# Adjustable_Positive_SupplyV3Switch.net
KiCad netlist of a schematic drawn in EAGLE
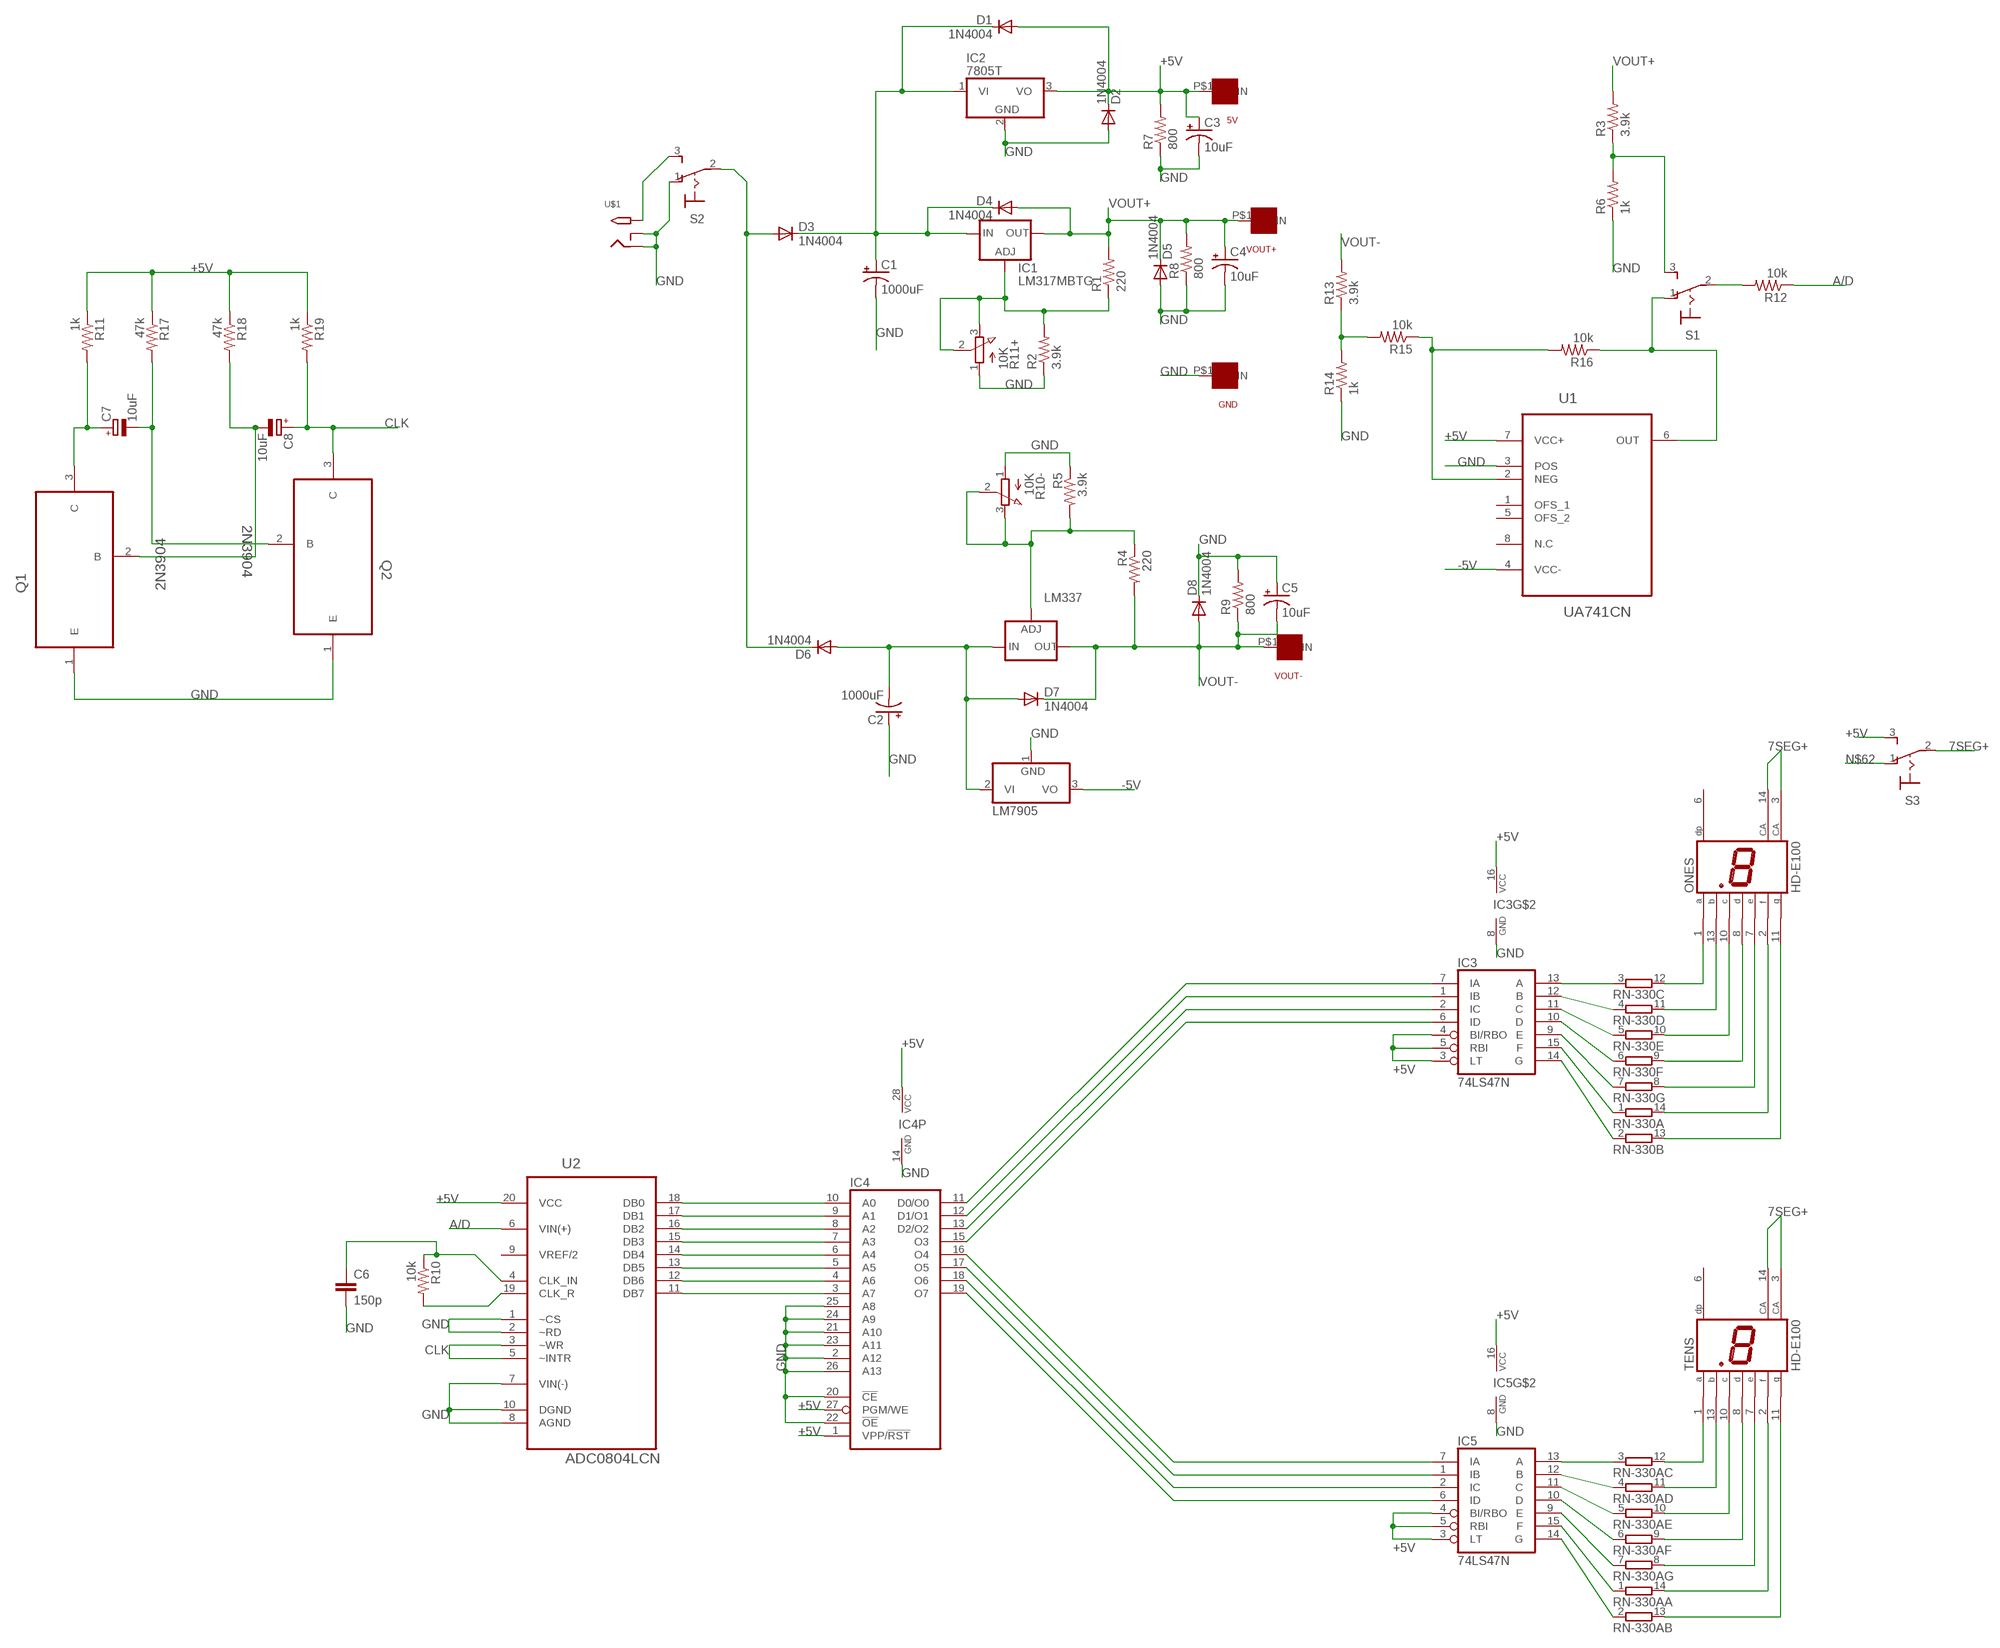
[diagram p0: schematic, sheet 1]

(export (version "E")
  (design (tool "Eeschema 10.0.6"))
  (components
    (comp (ref "5V")
      (value "TURRENT_TERMINAL")
      (footprint "eagle-import:TURRET_CONNECTOR")
      (libsource (lib "eagle-import") (part "TURRENT_TERMINAL"))
    )
    (comp (ref "C1")
      (value "1000uF")
      (footprint "eagle-import:E7,5-16")
      (libsource (lib "eagle-import") (part "CPOL-USE7.5-16"))
    )
    (comp (ref "C2")
      (value "1000uF")
      (footprint "eagle-import:E7,5-16")
      (libsource (lib "eagle-import") (part "CPOL-USE7.5-16"))
    )
    (comp (ref "C3")
      (value "10uF")
      (footprint "eagle-import:E2,5-5")
      (libsource (lib "eagle-import") (part "rcl_CPOL-USE2.5-5"))
    )
    (comp (ref "C4")
      (value "10uF")
      (footprint "eagle-import:E2,5-5")
      (libsource (lib "eagle-import") (part "rcl_CPOL-USE2.5-5"))
    )
    (comp (ref "C5")
      (value "10uF")
      (footprint "eagle-import:E2,5-5")
      (libsource (lib "eagle-import") (part "rcl_CPOL-USE2.5-5"))
    )
    (comp (ref "C6")
      (value "150p")
      (footprint "eagle-import:C025-025X050")
      (libsource (lib "eagle-import") (part "C-EU025-025X050"))
    )
    (comp (ref "C7")
      (value "10uF")
      (footprint "eagle-import:B45181B")
      (libsource (lib "eagle-import") (part "CPOL-EUB45181B"))
    )
    (comp (ref "C8")
      (value "10uF")
      (footprint "eagle-import:B45181B")
      (libsource (lib "eagle-import") (part "CPOL-EUB45181B"))
    )
    (comp (ref "D1")
      (value "1N4004")
      (footprint "eagle-import:DO41-10")
      (libsource (lib "eagle-import") (part "1N4004"))
    )
    (comp (ref "D2")
      (value "1N4004")
      (footprint "eagle-import:DO41-10")
      (libsource (lib "eagle-import") (part "1N4004"))
    )
    (comp (ref "D3")
      (value "1N4004")
      (footprint "eagle-import:DO41-10")
      (libsource (lib "eagle-import") (part "1N4004"))
    )
    (comp (ref "D4")
      (value "1N4004")
      (footprint "eagle-import:DO41-10")
      (libsource (lib "eagle-import") (part "1N4004"))
    )
    (comp (ref "D5")
      (value "1N4004")
      (footprint "eagle-import:DO41-10")
      (libsource (lib "eagle-import") (part "1N4004"))
    )
    (comp (ref "D6")
      (value "1N4004")
      (footprint "eagle-import:DO41-10")
      (libsource (lib "eagle-import") (part "1N4004"))
    )
    (comp (ref "D7")
      (value "1N4004")
      (footprint "eagle-import:DO41-10")
      (libsource (lib "eagle-import") (part "1N4004"))
    )
    (comp (ref "D8")
      (value "1N4004")
      (footprint "eagle-import:DO41-10")
      (libsource (lib "eagle-import") (part "1N4004"))
    )
    (comp (ref "GND")
      (value "TURRENT_TERMINAL")
      (footprint "eagle-import:TURRET_CONNECTOR")
      (libsource (lib "eagle-import") (part "TURRENT_TERMINAL"))
    )
    (comp (ref "IC1")
      (value "LM317MBTG")
      (footprint "eagle-import:TO220L1")
      (libsource (lib "eagle-import") (part "LM317?MBTG"))
    )
    (comp (ref "IC2")
      (value "7805T")
      (footprint "eagle-import:TO220H")
      (libsource (lib "eagle-import") (part "78T05"))
    )
    (comp (ref "IC3")
      (value "74LS47N")
      (footprint "eagle-import:DIL16")
      (libsource (lib "eagle-import") (part "7447NLS"))
    )
    (comp (ref "IC4")
      (value "27011")
      (footprint "eagle-import:DIL28")
      (libsource (lib "eagle-import") (part "27011"))
    )
    (comp (ref "IC5")
      (value "74LS47N")
      (footprint "eagle-import:DIL16")
      (libsource (lib "eagle-import") (part "7447NLS"))
    )
    (comp (ref "LM337")
      (value "LM337TL")
      (footprint "eagle-import:337TL")
      (libsource (lib "eagle-import") (part "LM337TL"))
    )
    (comp (ref "LM7905")
      (value "7905T")
      (footprint "eagle-import:TO220H")
      (libsource (lib "eagle-import") (part "79T05"))
    )
    (comp (ref "ONES")
      (value "HD-E100")
      (footprint "eagle-import:HDSP-I")
      (libsource (lib "eagle-import") (part "HD-E100"))
    )
    (comp (ref "Q1")
      (value "2N3904")
      (footprint "eagle-import:TO254P508X877-3")
      (libsource (lib "eagle-import") (part "2N3904"))
    )
    (comp (ref "Q2")
      (value "2N3904")
      (footprint "eagle-import:TO254P508X877-3")
      (libsource (lib "eagle-import") (part "2N3904"))
    )
    (comp (ref "R1")
      (value "220")
      (footprint "eagle-import:0411_15")
      (libsource (lib "eagle-import") (part "R-US_0411/15"))
    )
    (comp (ref "R2")
      (value "3.9k")
      (footprint "eagle-import:0411_15")
      (libsource (lib "eagle-import") (part "R-US_0411/15"))
    )
    (comp (ref "R3")
      (value "3.9k")
      (footprint "eagle-import:0411_15")
      (libsource (lib "eagle-import") (part "R-US_0411/15"))
    )
    (comp (ref "R4")
      (value "220")
      (footprint "eagle-import:0411_15")
      (libsource (lib "eagle-import") (part "R-US_0411/15"))
    )
    (comp (ref "R5")
      (value "3.9k")
      (footprint "eagle-import:0411_15")
      (libsource (lib "eagle-import") (part "R-US_0411/15"))
    )
    (comp (ref "R6")
      (value "1k")
      (footprint "eagle-import:0411_15")
      (libsource (lib "eagle-import") (part "R-US_0411/15"))
    )
    (comp (ref "R7")
      (value "800")
      (footprint "eagle-import:0411_15")
      (libsource (lib "eagle-import") (part "R-US_0411/15"))
    )
    (comp (ref "R8")
      (value "800")
      (footprint "eagle-import:0411_15")
      (libsource (lib "eagle-import") (part "R-US_0411/15"))
    )
    (comp (ref "R9")
      (value "800")
      (footprint "eagle-import:0411_15")
      (libsource (lib "eagle-import") (part "R-US_0411/15"))
    )
    (comp (ref "R10")
      (value "10k")
      (footprint "eagle-import:0411_15")
      (libsource (lib "eagle-import") (part "R-US_0411/15"))
    )
    (comp (ref "R10-")
      (value "10K")
      (footprint "eagle-import:EVUE")
      (libsource (lib "eagle-import") (part "EVUE2A"))
    )
    (comp (ref "R11")
      (value "1k")
      (footprint "eagle-import:0411_15")
      (libsource (lib "eagle-import") (part "R-US_0411/15"))
    )
    (comp (ref "R11+")
      (value "10K")
      (footprint "eagle-import:EVUE")
      (libsource (lib "eagle-import") (part "EVUE2A"))
    )
    (comp (ref "R12")
      (value "10k")
      (footprint "eagle-import:0411_15")
      (libsource (lib "eagle-import") (part "R-US_0411/15"))
    )
    (comp (ref "R13")
      (value "3.9k")
      (footprint "eagle-import:0411_15")
      (libsource (lib "eagle-import") (part "R-US_0411/15"))
    )
    (comp (ref "R14")
      (value "1k")
      (footprint "eagle-import:0411_15")
      (libsource (lib "eagle-import") (part "R-US_0411/15"))
    )
    (comp (ref "R15")
      (value "10k")
      (footprint "eagle-import:0411_15")
      (libsource (lib "eagle-import") (part "R-US_0411/15"))
    )
    (comp (ref "R16")
      (value "10k")
      (footprint "eagle-import:0411_15")
      (libsource (lib "eagle-import") (part "R-US_0411/15"))
    )
    (comp (ref "R17")
      (value "47k")
      (footprint "eagle-import:0411_15")
      (libsource (lib "eagle-import") (part "R-US_0411/15"))
    )
    (comp (ref "R18")
      (value "47k")
      (footprint "eagle-import:0411_15")
      (libsource (lib "eagle-import") (part "R-US_0411/15"))
    )
    (comp (ref "R19")
      (value "1k")
      (footprint "eagle-import:0411_15")
      (libsource (lib "eagle-import") (part "R-US_0411/15"))
    )
    (comp (ref "RN-330")
      (value "7R-N")
      (footprint "eagle-import:DIL14")
      (libsource (lib "eagle-import") (part "7R-N"))
    )
    (comp (ref "RN-330A")
      (value "7R-N")
      (footprint "eagle-import:DIL14")
      (libsource (lib "eagle-import") (part "7R-N"))
    )
    (comp (ref "S1")
      (value "M9040P")
      (footprint "eagle-import:M9040P")
      (libsource (lib "eagle-import") (part "M9040P"))
    )
    (comp (ref "S2")
      (value "M9040P")
      (footprint "eagle-import:M9040P")
      (libsource (lib "eagle-import") (part "M9040P"))
    )
    (comp (ref "S3")
      (value "M9040P")
      (footprint "eagle-import:M9040P")
      (libsource (lib "eagle-import") (part "M9040P"))
    )
    (comp (ref "TENS")
      (value "HD-E100")
      (footprint "eagle-import:HDSP-I")
      (libsource (lib "eagle-import") (part "HD-E100"))
    )
    (comp (ref "U$1")
      (value "2.1MMJACKTHM")
      (footprint "eagle-import:PJ-102A")
      (libsource (lib "eagle-import") (part "2.1MMJACKTHM"))
    )
    (comp (ref "U1")
      (value "UA741CN")
      (footprint "eagle-import:DIP254P762X533-8")
      (libsource (lib "eagle-import") (part "UA741CN"))
    )
    (comp (ref "U2")
      (value "ADC0804LCN")
      (footprint "eagle-import:DIP254P762X508-20")
      (libsource (lib "eagle-import") (part "ADC0804LCN"))
    )
    (comp (ref "VOUT+")
      (value "TURRENT_TERMINAL")
      (footprint "eagle-import:TURRET_CONNECTOR")
      (libsource (lib "eagle-import") (part "TURRENT_TERMINAL"))
    )
    (comp (ref "VOUT-")
      (value "TURRENT_TERMINAL")
      (footprint "eagle-import:TURRET_CONNECTOR")
      (libsource (lib "eagle-import") (part "TURRENT_TERMINAL"))
    )
  )
  (nets
    (net (code "1") (name "/+5V") (class "Default")
      (node (ref "5V") (pin "P$1") (pinfunction "IN_P$1") (pintype "bidirectional"))
      (node (ref "C3") (pin "+") (pinfunction "+_+") (pintype "passive"))
      (node (ref "D1") (pin "A") (pinfunction "A_A") (pintype "passive"))
      (node (ref "D2") (pin "C") (pinfunction "C_C") (pintype "passive"))
      (node (ref "IC2") (pin "3") (pinfunction "VO_3") (pintype "passive"))
      (node (ref "IC3") (pin "16") (pinfunction "VCC_16") (pintype "power_in"))
      (node (ref "IC3") (pin "3") (pinfunction "LT_3") (pintype "input"))
      (node (ref "IC3") (pin "4") (pinfunction "BI/RBO_4") (pintype "input"))
      (node (ref "IC3") (pin "5") (pinfunction "RBI_5") (pintype "input"))
      (node (ref "IC4") (pin "1") (pinfunction "VPP/~{RST}_1") (pintype "input"))
      (node (ref "IC4") (pin "27") (pinfunction "PGM/WE_27") (pintype "input"))
      (node (ref "IC4") (pin "28") (pinfunction "VCC_28") (pintype "power_in"))
      (node (ref "IC5") (pin "16") (pinfunction "VCC_16") (pintype "power_in"))
      (node (ref "IC5") (pin "3") (pinfunction "LT_3") (pintype "input"))
      (node (ref "IC5") (pin "4") (pinfunction "BI/RBO_4") (pintype "input"))
      (node (ref "IC5") (pin "5") (pinfunction "RBI_5") (pintype "input"))
      (node (ref "R11") (pin "1") (pinfunction "1_1") (pintype "passive"))
      (node (ref "R17") (pin "1") (pinfunction "1_1") (pintype "passive"))
      (node (ref "R18") (pin "1") (pinfunction "1_1") (pintype "passive"))
      (node (ref "R19") (pin "1") (pinfunction "1_1") (pintype "passive"))
      (node (ref "R7") (pin "2") (pinfunction "2_2") (pintype "passive"))
      (node (ref "S3") (pin "3") (pinfunction "S_3") (pintype "passive"))
      (node (ref "U1") (pin "7") (pinfunction "VCC+_7") (pintype "power_in"))
      (node (ref "U2") (pin "20") (pinfunction "VCC_20") (pintype "power_in"))
    )
    (net (code "2") (name "/-5V") (class "Default")
      (node (ref "LM7905") (pin "3") (pinfunction "VO_3") (pintype "passive"))
      (node (ref "U1") (pin "4") (pinfunction "VCC-_4") (pintype "power_in"))
    )
    (net (code "3") (name "/7SEG+") (class "Default")
      (node (ref "ONES") (pin "14") (pinfunction "CA_14") (pintype "passive"))
      (node (ref "ONES") (pin "3") (pinfunction "CA_3") (pintype "passive"))
      (node (ref "S3") (pin "2") (pinfunction "P_2") (pintype "passive"))
      (node (ref "TENS") (pin "14") (pinfunction "CA_14") (pintype "passive"))
      (node (ref "TENS") (pin "3") (pinfunction "CA_3") (pintype "passive"))
    )
    (net (code "4") (name "/A{slash}D") (class "Default")
      (node (ref "R12") (pin "1") (pinfunction "1_1") (pintype "passive"))
      (node (ref "U2") (pin "6") (pinfunction "VIN(+)_6") (pintype "power_in"))
    )
    (net (code "5") (name "/CLK") (class "Default")
      (node (ref "C8") (pin "+") (pinfunction "+_+") (pintype "passive"))
      (node (ref "Q2") (pin "3") (pinfunction "C_3") (pintype "passive"))
      (node (ref "R19") (pin "2") (pinfunction "2_2") (pintype "passive"))
      (node (ref "U2") (pin "3") (pinfunction "~{WR}_3") (pintype "input"))
      (node (ref "U2") (pin "5") (pinfunction "~{INTR}_5") (pintype "input"))
    )
    (net (code "6") (name "/GND") (class "Default")
      (node (ref "C1") (pin "-") (pinfunction "-_-") (pintype "passive"))
      (node (ref "C2") (pin "+") (pinfunction "+_+") (pintype "passive"))
      (node (ref "C3") (pin "-") (pinfunction "-_-") (pintype "passive"))
      (node (ref "C4") (pin "-") (pinfunction "-_-") (pintype "passive"))
      (node (ref "C5") (pin "+") (pinfunction "+_+") (pintype "passive"))
      (node (ref "C6") (pin "2") (pinfunction "2_2") (pintype "passive"))
      (node (ref "D2") (pin "A") (pinfunction "A_A") (pintype "passive"))
      (node (ref "D5") (pin "A") (pinfunction "A_A") (pintype "passive"))
      (node (ref "D8") (pin "C") (pinfunction "C_C") (pintype "passive"))
      (node (ref "GND") (pin "P$1") (pinfunction "IN_P$1") (pintype "bidirectional"))
      (node (ref "IC2") (pin "2") (pinfunction "GND_2") (pintype "passive"))
      (node (ref "IC3") (pin "8") (pinfunction "GND_8") (pintype "power_in"))
      (node (ref "IC4") (pin "14") (pinfunction "GND_14") (pintype "power_in"))
      (node (ref "IC4") (pin "2") (pinfunction "A12_2") (pintype "input"))
      (node (ref "IC4") (pin "20") (pinfunction "~{CE}_20") (pintype "input"))
      (node (ref "IC4") (pin "21") (pinfunction "A10_21") (pintype "input"))
      (node (ref "IC4") (pin "22") (pinfunction "~{OE}_22") (pintype "input"))
      (node (ref "IC4") (pin "23") (pinfunction "A11_23") (pintype "input"))
      (node (ref "IC4") (pin "24") (pinfunction "A9_24") (pintype "input"))
      (node (ref "IC4") (pin "25") (pinfunction "A8_25") (pintype "input"))
      (node (ref "IC4") (pin "26") (pinfunction "A13_26") (pintype "input"))
      (node (ref "IC5") (pin "8") (pinfunction "GND_8") (pintype "power_in"))
      (node (ref "LM7905") (pin "1") (pinfunction "GND_1") (pintype "passive"))
      (node (ref "Q1") (pin "1") (pinfunction "E_1") (pintype "passive"))
      (node (ref "Q2") (pin "1") (pinfunction "E_1") (pintype "passive"))
      (node (ref "R10-") (pin "1") (pinfunction "A_1") (pintype "passive"))
      (node (ref "R11+") (pin "1") (pinfunction "A_1") (pintype "passive"))
      (node (ref "R14") (pin "1") (pinfunction "1_1") (pintype "passive"))
      (node (ref "R2") (pin "1") (pinfunction "1_1") (pintype "passive"))
      (node (ref "R5") (pin "1") (pinfunction "1_1") (pintype "passive"))
      (node (ref "R6") (pin "1") (pinfunction "1_1") (pintype "passive"))
      (node (ref "R7") (pin "1") (pinfunction "1_1") (pintype "passive"))
      (node (ref "R8") (pin "1") (pinfunction "1_1") (pintype "passive"))
      (node (ref "R9") (pin "2") (pinfunction "2_2") (pintype "passive"))
      (node (ref "S2") (pin "1") (pinfunction "O_1") (pintype "passive"))
      (node (ref "U$1") (pin "RING") (pinfunction "RING_RING") (pintype "bidirectional"))
      (node (ref "U$1") (pin "RING_SW") (pinfunction "RING_SW_RING_SW") (pintype "bidirectional"))
      (node (ref "U1") (pin "3") (pinfunction "POS_3") (pintype "input"))
      (node (ref "U2") (pin "1") (pinfunction "~{CS}_1") (pintype "input"))
      (node (ref "U2") (pin "10") (pinfunction "DGND_10") (pintype "passive"))
      (node (ref "U2") (pin "2") (pinfunction "~{RD}_2") (pintype "input"))
      (node (ref "U2") (pin "7") (pinfunction "VIN(-)_7") (pintype "power_in"))
      (node (ref "U2") (pin "8") (pinfunction "AGND_8") (pintype "passive"))
    )
    (net (code "7") (name "/N$62") (class "Default")
      (node (ref "S3") (pin "1") (pinfunction "O_1") (pintype "passive"))
    )
    (net (code "8") (name "/VOUT+") (class "Default")
      (node (ref "C4") (pin "+") (pinfunction "+_+") (pintype "passive"))
      (node (ref "D4") (pin "A") (pinfunction "A_A") (pintype "passive"))
      (node (ref "D5") (pin "C") (pinfunction "C_C") (pintype "passive"))
      (node (ref "IC1") (pin "2") (pinfunction "OUT_2") (pintype "passive"))
      (node (ref "R1") (pin "2") (pinfunction "2_2") (pintype "passive"))
      (node (ref "R3") (pin "2") (pinfunction "2_2") (pintype "passive"))
      (node (ref "R8") (pin "2") (pinfunction "2_2") (pintype "passive"))
      (node (ref "VOUT+") (pin "P$1") (pinfunction "IN_P$1") (pintype "bidirectional"))
    )
    (net (code "9") (name "/VOUT-") (class "Default")
      (node (ref "C5") (pin "-") (pinfunction "-_-") (pintype "passive"))
      (node (ref "D7") (pin "C") (pinfunction "C_C") (pintype "passive"))
      (node (ref "D8") (pin "A") (pinfunction "A_A") (pintype "passive"))
      (node (ref "LM337") (pin "3") (pinfunction "OUT_3") (pintype "passive"))
      (node (ref "R13") (pin "2") (pinfunction "2_2") (pintype "passive"))
      (node (ref "R4") (pin "2") (pinfunction "2_2") (pintype "passive"))
      (node (ref "R9") (pin "1") (pinfunction "1_1") (pintype "passive"))
      (node (ref "VOUT-") (pin "P$1") (pinfunction "IN_P$1") (pintype "bidirectional"))
    )
    (net (code "10") (name "Net-(IC1-ADJ)") (class "Default")
      (node (ref "IC1") (pin "1") (pinfunction "ADJ_1") (pintype "input"))
      (node (ref "R1") (pin "1") (pinfunction "1_1") (pintype "passive"))
      (node (ref "R11+") (pin "2") (pinfunction "S_2") (pintype "passive"))
      (node (ref "R11+") (pin "3") (pinfunction "E_3") (pintype "passive"))
      (node (ref "R2") (pin "2") (pinfunction "2_2") (pintype "passive"))
    )
    (net (code "11") (name "Net-(IC1-IN)") (class "Default")
      (node (ref "C1") (pin "+") (pinfunction "+_+") (pintype "passive"))
      (node (ref "D1") (pin "C") (pinfunction "C_C") (pintype "passive"))
      (node (ref "D3") (pin "C") (pinfunction "C_C") (pintype "passive"))
      (node (ref "D4") (pin "C") (pinfunction "C_C") (pintype "passive"))
      (node (ref "IC1") (pin "3") (pinfunction "IN_3") (pintype "input"))
      (node (ref "IC2") (pin "1") (pinfunction "VI_1") (pintype "input"))
    )
    (net (code "12") (name "Net-(IC3A-A)") (class "Default")
      (node (ref "IC3") (pin "13") (pinfunction "A_13") (pintype "output"))
      (node (ref "RN-330") (pin "3") (pinfunction "1_3") (pintype "passive"))
    )
    (net (code "13") (name "Net-(IC3A-B)") (class "Default")
      (node (ref "IC3") (pin "12") (pinfunction "B_12") (pintype "output"))
      (node (ref "RN-330") (pin "4") (pinfunction "1_4") (pintype "passive"))
    )
    (net (code "14") (name "Net-(IC3A-C)") (class "Default")
      (node (ref "IC3") (pin "11") (pinfunction "C_11") (pintype "output"))
      (node (ref "RN-330") (pin "5") (pinfunction "1_5") (pintype "passive"))
    )
    (net (code "15") (name "Net-(IC3A-D)") (class "Default")
      (node (ref "IC3") (pin "10") (pinfunction "D_10") (pintype "output"))
      (node (ref "RN-330") (pin "6") (pinfunction "1_6") (pintype "passive"))
    )
    (net (code "16") (name "Net-(IC3A-E)") (class "Default")
      (node (ref "IC3") (pin "9") (pinfunction "E_9") (pintype "output"))
      (node (ref "RN-330") (pin "7") (pinfunction "1_7") (pintype "passive"))
    )
    (net (code "17") (name "Net-(IC3A-F)") (class "Default")
      (node (ref "IC3") (pin "15") (pinfunction "F_15") (pintype "output"))
      (node (ref "RN-330") (pin "1") (pinfunction "1_1") (pintype "passive"))
    )
    (net (code "18") (name "Net-(IC3A-G)") (class "Default")
      (node (ref "IC3") (pin "14") (pinfunction "G_14") (pintype "output"))
      (node (ref "RN-330") (pin "2") (pinfunction "1_2") (pintype "passive"))
    )
    (net (code "19") (name "Net-(IC3A-IA)") (class "Default")
      (node (ref "IC3") (pin "7") (pinfunction "IA_7") (pintype "input"))
      (node (ref "IC4") (pin "11") (pinfunction "D0/O0_11") (pintype "tri_state"))
    )
    (net (code "20") (name "Net-(IC3A-IB)") (class "Default")
      (node (ref "IC3") (pin "1") (pinfunction "IB_1") (pintype "input"))
      (node (ref "IC4") (pin "12") (pinfunction "D1/O1_12") (pintype "tri_state"))
    )
    (net (code "21") (name "Net-(IC3A-IC)") (class "Default")
      (node (ref "IC3") (pin "2") (pinfunction "IC_2") (pintype "input"))
      (node (ref "IC4") (pin "13") (pinfunction "D2/O2_13") (pintype "tri_state"))
    )
    (net (code "22") (name "Net-(IC3A-ID)") (class "Default")
      (node (ref "IC3") (pin "6") (pinfunction "ID_6") (pintype "input"))
      (node (ref "IC4") (pin "15") (pinfunction "O3_15") (pintype "tri_state"))
    )
    (net (code "23") (name "Net-(IC4A-A0)") (class "Default")
      (node (ref "IC4") (pin "10") (pinfunction "A0_10") (pintype "input"))
      (node (ref "U2") (pin "18") (pinfunction "DB0_18") (pintype "passive"))
    )
    (net (code "24") (name "Net-(IC4A-A1)") (class "Default")
      (node (ref "IC4") (pin "9") (pinfunction "A1_9") (pintype "input"))
      (node (ref "U2") (pin "17") (pinfunction "DB1_17") (pintype "passive"))
    )
    (net (code "25") (name "Net-(IC4A-A2)") (class "Default")
      (node (ref "IC4") (pin "8") (pinfunction "A2_8") (pintype "input"))
      (node (ref "U2") (pin "16") (pinfunction "DB2_16") (pintype "passive"))
    )
    (net (code "26") (name "Net-(IC4A-A3)") (class "Default")
      (node (ref "IC4") (pin "7") (pinfunction "A3_7") (pintype "input"))
      (node (ref "U2") (pin "15") (pinfunction "DB3_15") (pintype "passive"))
    )
    (net (code "27") (name "Net-(IC4A-A4)") (class "Default")
      (node (ref "IC4") (pin "6") (pinfunction "A4_6") (pintype "input"))
      (node (ref "U2") (pin "14") (pinfunction "DB4_14") (pintype "passive"))
    )
    (net (code "28") (name "Net-(IC4A-A5)") (class "Default")
      (node (ref "IC4") (pin "5") (pinfunction "A5_5") (pintype "input"))
      (node (ref "U2") (pin "13") (pinfunction "DB5_13") (pintype "passive"))
    )
    (net (code "29") (name "Net-(IC4A-A6)") (class "Default")
      (node (ref "IC4") (pin "4") (pinfunction "A6_4") (pintype "input"))
      (node (ref "U2") (pin "12") (pinfunction "DB6_12") (pintype "passive"))
    )
    (net (code "30") (name "Net-(IC4A-A7)") (class "Default")
      (node (ref "IC4") (pin "3") (pinfunction "A7_3") (pintype "input"))
      (node (ref "U2") (pin "11") (pinfunction "DB7_11") (pintype "passive"))
    )
    (net (code "31") (name "Net-(IC4A-O4)") (class "Default")
      (node (ref "IC4") (pin "16") (pinfunction "O4_16") (pintype "tri_state"))
      (node (ref "IC5") (pin "7") (pinfunction "IA_7") (pintype "input"))
    )
    (net (code "32") (name "Net-(IC4A-O5)") (class "Default")
      (node (ref "IC4") (pin "17") (pinfunction "O5_17") (pintype "tri_state"))
      (node (ref "IC5") (pin "1") (pinfunction "IB_1") (pintype "input"))
    )
    (net (code "33") (name "Net-(IC4A-O6)") (class "Default")
      (node (ref "IC4") (pin "18") (pinfunction "O6_18") (pintype "tri_state"))
      (node (ref "IC5") (pin "2") (pinfunction "IC_2") (pintype "input"))
    )
    (net (code "34") (name "Net-(IC4A-O7)") (class "Default")
      (node (ref "IC4") (pin "19") (pinfunction "O7_19") (pintype "tri_state"))
      (node (ref "IC5") (pin "6") (pinfunction "ID_6") (pintype "input"))
    )
    (net (code "35") (name "Net-(IC5A-A)") (class "Default")
      (node (ref "IC5") (pin "13") (pinfunction "A_13") (pintype "output"))
      (node (ref "RN-330A") (pin "3") (pinfunction "1_3") (pintype "passive"))
    )
    (net (code "36") (name "Net-(IC5A-B)") (class "Default")
      (node (ref "IC5") (pin "12") (pinfunction "B_12") (pintype "output"))
      (node (ref "RN-330A") (pin "4") (pinfunction "1_4") (pintype "passive"))
    )
    (net (code "37") (name "Net-(IC5A-C)") (class "Default")
      (node (ref "IC5") (pin "11") (pinfunction "C_11") (pintype "output"))
      (node (ref "RN-330A") (pin "5") (pinfunction "1_5") (pintype "passive"))
    )
    (net (code "38") (name "Net-(IC5A-D)") (class "Default")
      (node (ref "IC5") (pin "10") (pinfunction "D_10") (pintype "output"))
      (node (ref "RN-330A") (pin "6") (pinfunction "1_6") (pintype "passive"))
    )
    (net (code "39") (name "Net-(IC5A-E)") (class "Default")
      (node (ref "IC5") (pin "9") (pinfunction "E_9") (pintype "output"))
      (node (ref "RN-330A") (pin "7") (pinfunction "1_7") (pintype "passive"))
    )
    (net (code "40") (name "Net-(IC5A-F)") (class "Default")
      (node (ref "IC5") (pin "15") (pinfunction "F_15") (pintype "output"))
      (node (ref "RN-330A") (pin "1") (pinfunction "1_1") (pintype "passive"))
    )
    (net (code "41") (name "Net-(IC5A-G)") (class "Default")
      (node (ref "IC5") (pin "14") (pinfunction "G_14") (pintype "output"))
      (node (ref "RN-330A") (pin "2") (pinfunction "1_2") (pintype "passive"))
    )
    (net (code "42") (name "Net-(LM337-ADJ)") (class "Default")
      (node (ref "LM337") (pin "1") (pinfunction "ADJ_1") (pintype "input"))
      (node (ref "R10-") (pin "2") (pinfunction "S_2") (pintype "passive"))
      (node (ref "R10-") (pin "3") (pinfunction "E_3") (pintype "passive"))
      (node (ref "R4") (pin "1") (pinfunction "1_1") (pintype "passive"))
      (node (ref "R5") (pin "2") (pinfunction "2_2") (pintype "passive"))
    )
    (net (code "43") (name "Net-(LM337-IN)") (class "Default")
      (node (ref "C2") (pin "-") (pinfunction "-_-") (pintype "passive"))
      (node (ref "D6") (pin "A") (pinfunction "A_A") (pintype "passive"))
      (node (ref "D7") (pin "A") (pinfunction "A_A") (pintype "passive"))
      (node (ref "LM337") (pin "2") (pinfunction "IN_2") (pintype "input"))
      (node (ref "LM7905") (pin "2") (pinfunction "VI_2") (pintype "input"))
    )
    (net (code "44") (name "Net-(ONES-A)") (class "Default")
      (node (ref "ONES") (pin "1") (pinfunction "A_1") (pintype "passive"))
      (node (ref "RN-330") (pin "12") (pinfunction "2_12") (pintype "passive"))
    )
    (net (code "45") (name "Net-(ONES-B)") (class "Default")
      (node (ref "ONES") (pin "13") (pinfunction "B_13") (pintype "passive"))
      (node (ref "RN-330") (pin "11") (pinfunction "2_11") (pintype "passive"))
    )
    (net (code "46") (name "Net-(ONES-C)") (class "Default")
      (node (ref "ONES") (pin "10") (pinfunction "C_10") (pintype "passive"))
      (node (ref "RN-330") (pin "10") (pinfunction "2_10") (pintype "passive"))
    )
    (net (code "47") (name "Net-(ONES-D)") (class "Default")
      (node (ref "ONES") (pin "8") (pinfunction "D_8") (pintype "passive"))
      (node (ref "RN-330") (pin "9") (pinfunction "2_9") (pintype "passive"))
    )
    (net (code "48") (name "Net-(ONES-E)") (class "Default")
      (node (ref "ONES") (pin "7") (pinfunction "E_7") (pintype "passive"))
      (node (ref "RN-330") (pin "8") (pinfunction "2_8") (pintype "passive"))
    )
    (net (code "49") (name "Net-(ONES-F)") (class "Default")
      (node (ref "ONES") (pin "2") (pinfunction "F_2") (pintype "passive"))
      (node (ref "RN-330") (pin "14") (pinfunction "2_14") (pintype "passive"))
    )
    (net (code "50") (name "Net-(ONES-G)") (class "Default")
      (node (ref "ONES") (pin "11") (pinfunction "G_11") (pintype "passive"))
      (node (ref "RN-330") (pin "13") (pinfunction "2_13") (pintype "passive"))
    )
    (net (code "51") (name "Net-(Q1-B)") (class "Default")
      (node (ref "C8") (pin "-") (pinfunction "-_-") (pintype "passive"))
      (node (ref "Q1") (pin "2") (pinfunction "B_2") (pintype "passive"))
      (node (ref "R18") (pin "2") (pinfunction "2_2") (pintype "passive"))
    )
    (net (code "52") (name "Net-(Q1-C)") (class "Default")
      (node (ref "C7") (pin "+") (pinfunction "+_+") (pintype "passive"))
      (node (ref "Q1") (pin "3") (pinfunction "C_3") (pintype "passive"))
      (node (ref "R11") (pin "2") (pinfunction "2_2") (pintype "passive"))
    )
    (net (code "53") (name "Net-(Q2-B)") (class "Default")
      (node (ref "C7") (pin "-") (pinfunction "-_-") (pintype "passive"))
      (node (ref "Q2") (pin "2") (pinfunction "B_2") (pintype "passive"))
      (node (ref "R17") (pin "2") (pinfunction "2_2") (pintype "passive"))
    )
    (net (code "54") (name "Net-(R13-Pad1)") (class "Default")
      (node (ref "R13") (pin "1") (pinfunction "1_1") (pintype "passive"))
      (node (ref "R14") (pin "2") (pinfunction "2_2") (pintype "passive"))
      (node (ref "R15") (pin "2") (pinfunction "2_2") (pintype "passive"))
    )
    (net (code "55") (name "Net-(RN-330AA-2)") (class "Default")
      (node (ref "RN-330A") (pin "14") (pinfunction "2_14") (pintype "passive"))
      (node (ref "TENS") (pin "2") (pinfunction "F_2") (pintype "passive"))
    )
    (net (code "56") (name "Net-(RN-330AB-2)") (class "Default")
      (node (ref "RN-330A") (pin "13") (pinfunction "2_13") (pintype "passive"))
      (node (ref "TENS") (pin "11") (pinfunction "G_11") (pintype "passive"))
    )
    (net (code "57") (name "Net-(RN-330AC-2)") (class "Default")
      (node (ref "RN-330A") (pin "12") (pinfunction "2_12") (pintype "passive"))
      (node (ref "TENS") (pin "1") (pinfunction "A_1") (pintype "passive"))
    )
    (net (code "58") (name "Net-(RN-330AD-2)") (class "Default")
      (node (ref "RN-330A") (pin "11") (pinfunction "2_11") (pintype "passive"))
      (node (ref "TENS") (pin "13") (pinfunction "B_13") (pintype "passive"))
    )
    (net (code "59") (name "Net-(RN-330AE-2)") (class "Default")
      (node (ref "RN-330A") (pin "10") (pinfunction "2_10") (pintype "passive"))
      (node (ref "TENS") (pin "10") (pinfunction "C_10") (pintype "passive"))
    )
    (net (code "60") (name "Net-(RN-330AF-2)") (class "Default")
      (node (ref "RN-330A") (pin "9") (pinfunction "2_9") (pintype "passive"))
      (node (ref "TENS") (pin "8") (pinfunction "D_8") (pintype "passive"))
    )
    (net (code "61") (name "Net-(RN-330AG-2)") (class "Default")
      (node (ref "RN-330A") (pin "8") (pinfunction "2_8") (pintype "passive"))
      (node (ref "TENS") (pin "7") (pinfunction "E_7") (pintype "passive"))
    )
    (net (code "62") (name "Net-(S1-O)") (class "Default")
      (node (ref "R16") (pin "1") (pinfunction "1_1") (pintype "passive"))
      (node (ref "S1") (pin "1") (pinfunction "O_1") (pintype "passive"))
      (node (ref "U1") (pin "6") (pinfunction "OUT_6") (pintype "output"))
    )
    (net (code "63") (name "Net-(S1-P)") (class "Default")
      (node (ref "R12") (pin "2") (pinfunction "2_2") (pintype "passive"))
      (node (ref "S1") (pin "2") (pinfunction "P_2") (pintype "passive"))
    )
    (net (code "64") (name "Net-(S1-S)") (class "Default")
      (node (ref "R3") (pin "1") (pinfunction "1_1") (pintype "passive"))
      (node (ref "R6") (pin "2") (pinfunction "2_2") (pintype "passive"))
      (node (ref "S1") (pin "3") (pinfunction "S_3") (pintype "passive"))
    )
    (net (code "65") (name "Net-(S2-P)") (class "Default")
      (node (ref "D3") (pin "A") (pinfunction "A_A") (pintype "passive"))
      (node (ref "D6") (pin "C") (pinfunction "C_C") (pintype "passive"))
      (node (ref "S2") (pin "2") (pinfunction "P_2") (pintype "passive"))
    )
    (net (code "66") (name "Net-(S2-S)") (class "Default")
      (node (ref "S2") (pin "3") (pinfunction "S_3") (pintype "passive"))
      (node (ref "U$1") (pin "TIP") (pinfunction "TIP_TIP") (pintype "bidirectional"))
    )
    (net (code "67") (name "Net-(U1-NEG)") (class "Default")
      (node (ref "R15") (pin "1") (pinfunction "1_1") (pintype "passive"))
      (node (ref "R16") (pin "2") (pinfunction "2_2") (pintype "passive"))
      (node (ref "U1") (pin "2") (pinfunction "NEG_2") (pintype "input"))
    )
    (net (code "68") (name "Net-(U2-CLK_IN)") (class "Default")
      (node (ref "C6") (pin "1") (pinfunction "1_1") (pintype "passive"))
      (node (ref "R10") (pin "1") (pinfunction "1_1") (pintype "passive"))
      (node (ref "U2") (pin "4") (pinfunction "CLK_IN_4") (pintype "input"))
    )
    (net (code "69") (name "Net-(U2-CLK_R)") (class "Default")
      (node (ref "R10") (pin "2") (pinfunction "2_2") (pintype "passive"))
      (node (ref "U2") (pin "19") (pinfunction "CLK_R_19") (pintype "input"))
    )
    (net (code "70") (name "unconnected-(ONES-DP-Pad6)") (class "Default")
      (node (ref "ONES") (pin "6") (pinfunction "DP_6") (pintype "passive"))
    )
    (net (code "71") (name "unconnected-(TENS-DP-Pad6)") (class "Default")
      (node (ref "TENS") (pin "6") (pinfunction "DP_6") (pintype "passive"))
    )
    (net (code "72") (name "unconnected-(U1-N.C-Pad8)") (class "Default")
      (node (ref "U1") (pin "8") (pinfunction "N.C_8") (pintype "no_connect"))
    )
    (net (code "73") (name "unconnected-(U1-OFS_1-Pad1)") (class "Default")
      (node (ref "U1") (pin "1") (pinfunction "OFS_1_1") (pintype "passive"))
    )
    (net (code "74") (name "unconnected-(U1-OFS_2-Pad5)") (class "Default")
      (node (ref "U1") (pin "5") (pinfunction "OFS_2_5") (pintype "passive"))
    )
    (net (code "75") (name "unconnected-(U2-VREF{slash}2-Pad9)") (class "Default")
      (node (ref "U2") (pin "9") (pinfunction "VREF/2_9") (pintype "input"))
    )
  )
)
